# ProPrj_E73__2025-03-08.net
KiCad netlist of a schematic drawn in EasyEDA Pro
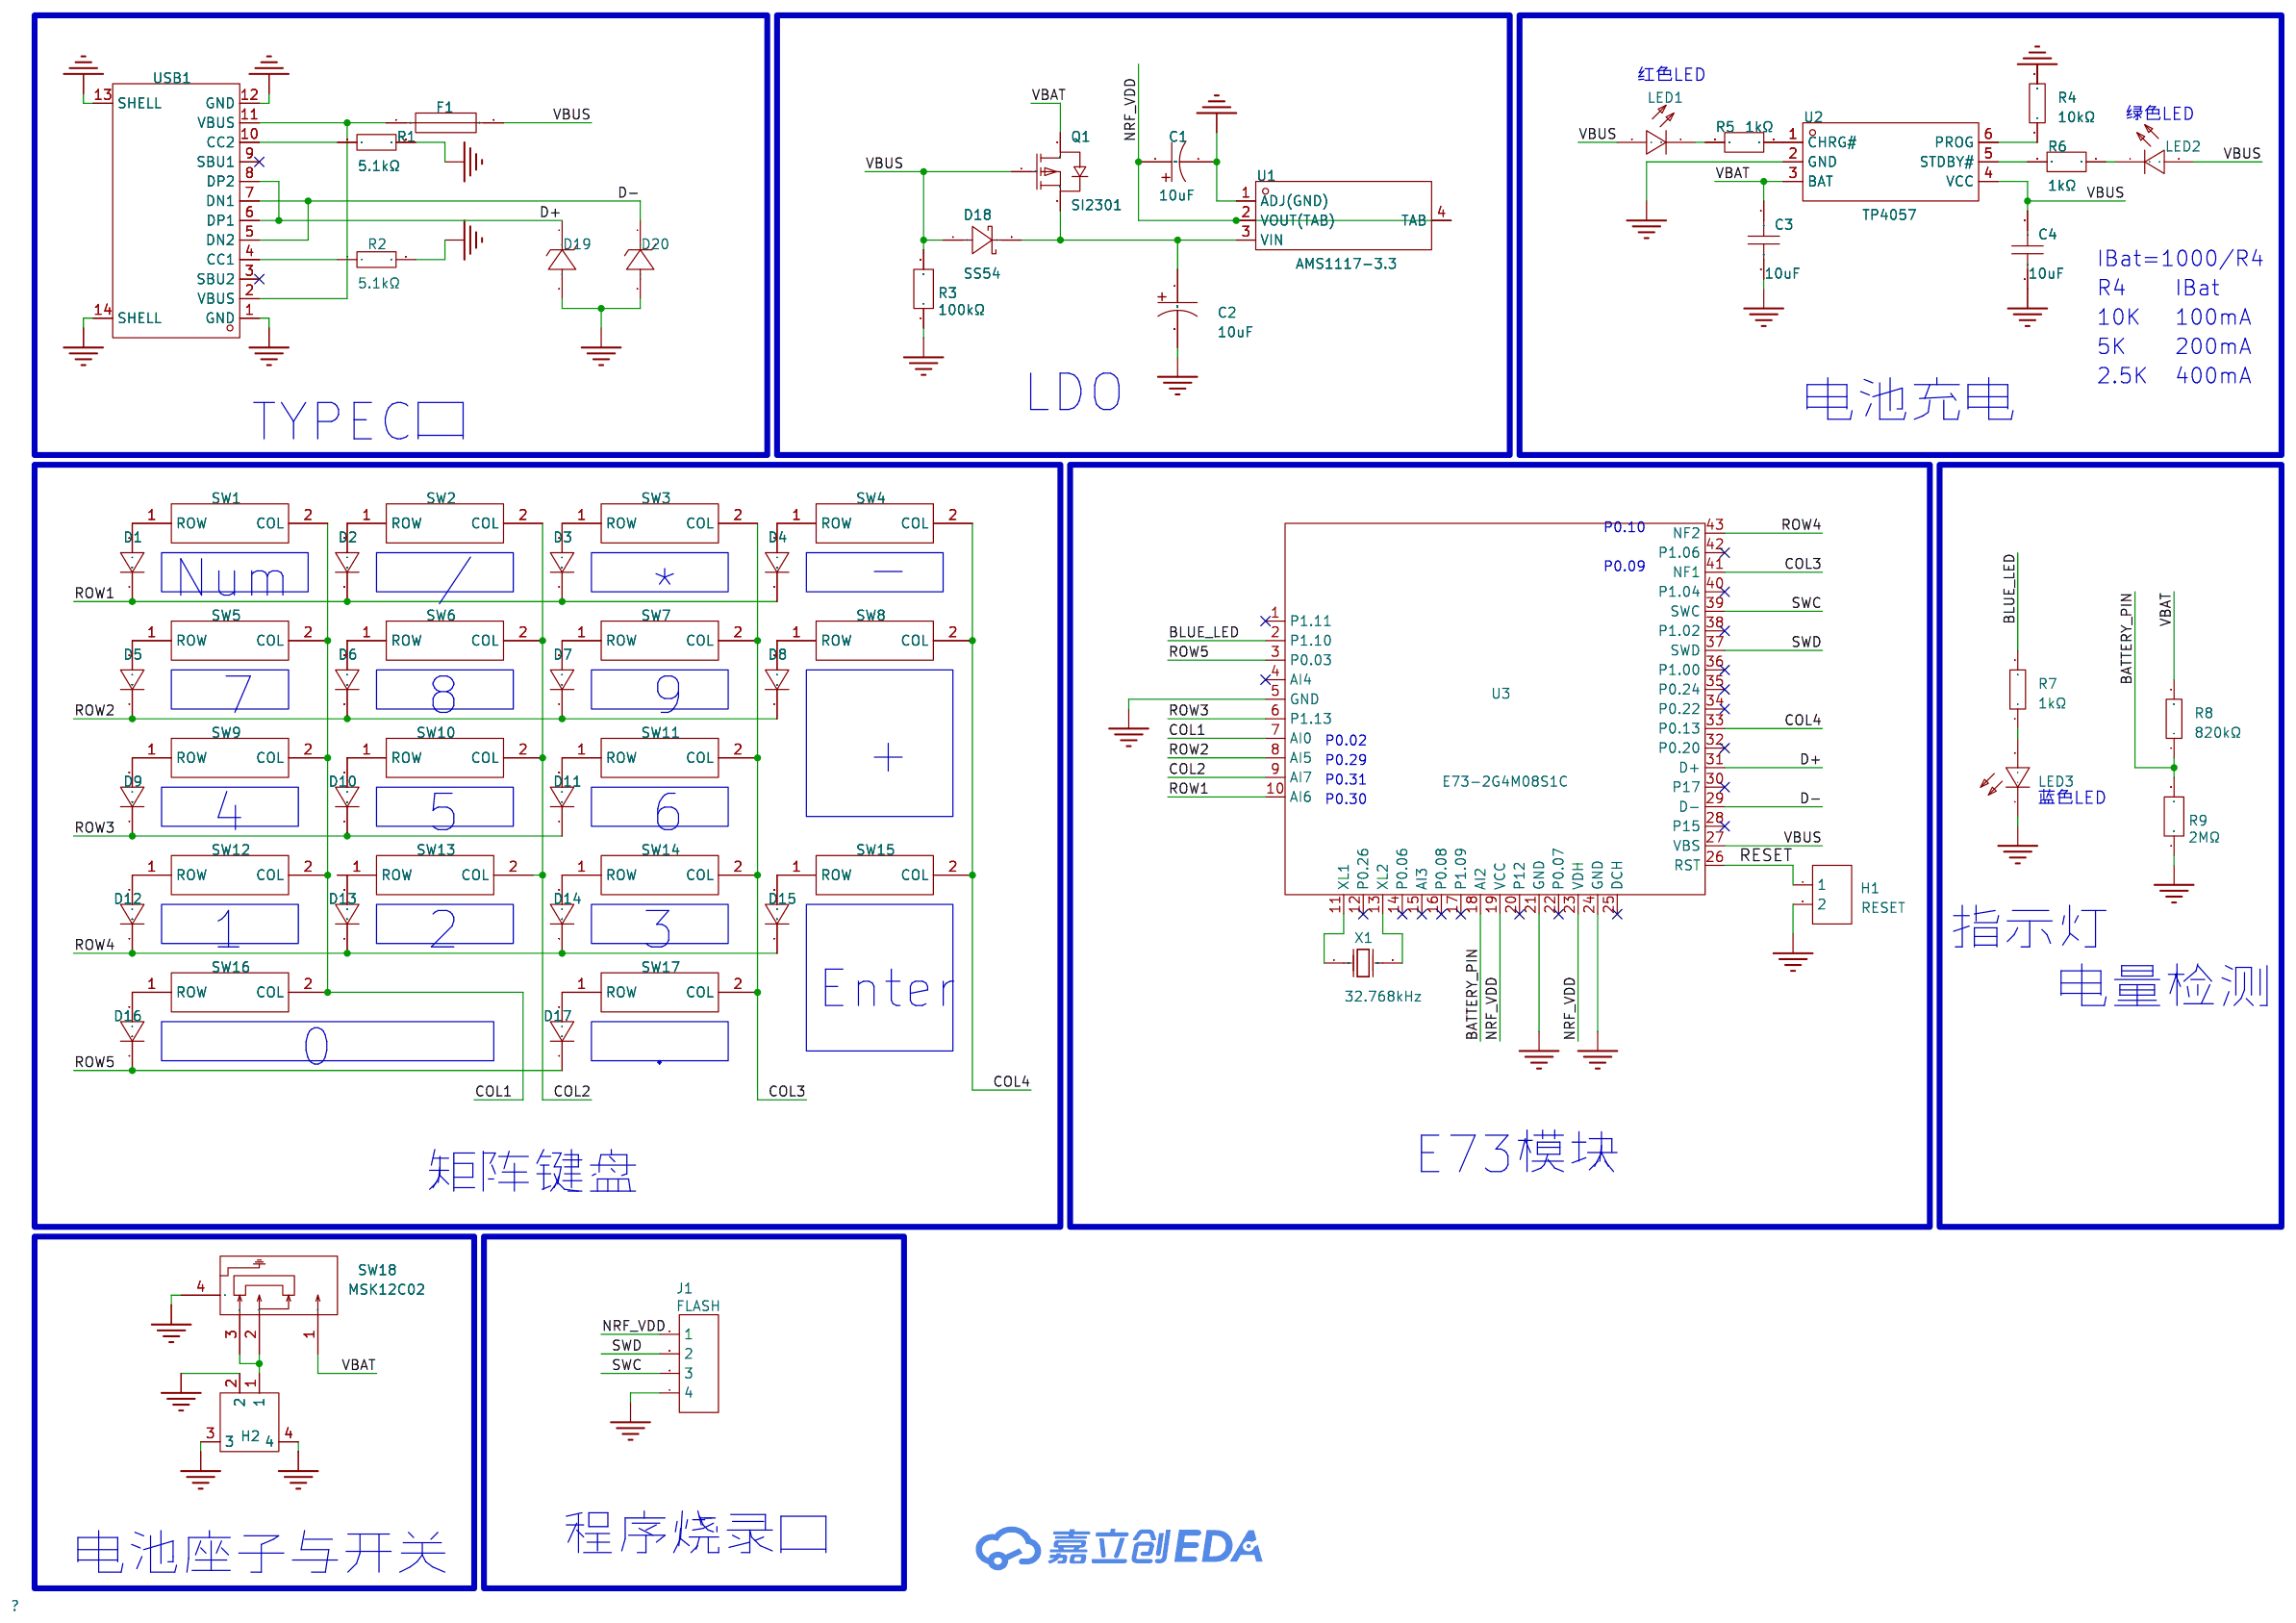
[diagram p0: schematic sheet]

(export (version "E")
  (design (tool "Eeschema 10.0.6"))
  (components
    (comp (ref "C1")
      (value "10uF")
      (footprint "easyedapro:CAP-SMD_L3.2-W1.6")
      (description "容值:10uF;精度:±10%;额定电压:16V;等效串联电阻:2Ω@100kHz;")
      (fields
        (field (name "Manufacturer Part") "CA45-A-16V-10μF-K")
        (field (name "Manufacturer") "TORCH(火炬)")
      )
      (libsource (lib "easyedapro") (part "CA45-A-16V-10μF-K"))
    )
    (comp (ref "C2")
      (value "10uF")
      (footprint "easyedapro:CAP-SMD_L3.2-W1.6")
      (description "容值:10uF;精度:±10%;额定电压:16V;等效串联电阻:2Ω@100kHz;")
      (fields
        (field (name "Manufacturer Part") "CA45-A-16V-10μF-K")
        (field (name "Manufacturer") "TORCH(火炬)")
      )
      (libsource (lib "easyedapro") (part "CA45-A-16V-10μF-K"))
    )
    (comp (ref "C3")
      (value "10uF")
      (footprint "easyedapro:C0603")
      (description "容值:10uF;精度:±20%;额定电压:16V;材质(温度系数):X5R;")
      (fields
        (field (name "Manufacturer Part") "HGC0603R5106M160NTHJ")
        (field (name "Manufacturer") "Chinocera(华瓷)")
      )
      (libsource (lib "easyedapro") (part "HGC0603R5106M160NTHJ"))
    )
    (comp (ref "C4")
      (value "10uF")
      (footprint "easyedapro:C0603")
      (description "容值:10uF;精度:±20%;额定电压:16V;材质(温度系数):X5R;")
      (fields
        (field (name "Manufacturer Part") "HGC0603R5106M160NTHJ")
        (field (name "Manufacturer") "Chinocera(华瓷)")
      )
      (libsource (lib "easyedapro") (part "HGC0603R5106M160NTHJ"))
    )
    (comp (ref "D1")
      (value "LL4148")
      (footprint "easyedapro:LL-34_L3.5-W1.5-RD")
      (description "二极管配置:-;正向压降(Vf):1V@10mA;直流反向耐压(Vr):75V;整流电流:200mA;反向恢复时间(trr):4ns;")
      (fields (field (name "Manufacturer") "MDD(辰达半导体)"))
      (libsource (lib "easyedapro") (part "LL4148_C435829"))
    )
    (comp (ref "D2")
      (value "LL4148")
      (footprint "easyedapro:LL-34_L3.5-W1.5-RD")
      (description "二极管配置:-;正向压降(Vf):1V@10mA;直流反向耐压(Vr):75V;整流电流:200mA;反向恢复时间(trr):4ns;")
      (fields (field (name "Manufacturer") "MDD(辰达半导体)"))
      (libsource (lib "easyedapro") (part "LL4148_C435829"))
    )
    (comp (ref "D3")
      (value "LL4148")
      (footprint "easyedapro:LL-34_L3.5-W1.5-RD")
      (description "二极管配置:-;正向压降(Vf):1V@10mA;直流反向耐压(Vr):75V;整流电流:200mA;反向恢复时间(trr):4ns;")
      (fields (field (name "Manufacturer") "MDD(辰达半导体)"))
      (libsource (lib "easyedapro") (part "LL4148_C435829"))
    )
    (comp (ref "D4")
      (value "LL4148")
      (footprint "easyedapro:LL-34_L3.5-W1.5-RD")
      (description "二极管配置:-;正向压降(Vf):1V@10mA;直流反向耐压(Vr):75V;整流电流:200mA;反向恢复时间(trr):4ns;")
      (fields (field (name "Manufacturer") "MDD(辰达半导体)"))
      (libsource (lib "easyedapro") (part "LL4148_C435829"))
    )
    (comp (ref "D5")
      (value "LL4148")
      (footprint "easyedapro:LL-34_L3.5-W1.5-RD")
      (description "二极管配置:-;正向压降(Vf):1V@10mA;直流反向耐压(Vr):75V;整流电流:200mA;反向恢复时间(trr):4ns;")
      (fields (field (name "Manufacturer") "MDD(辰达半导体)"))
      (libsource (lib "easyedapro") (part "LL4148_C435829"))
    )
    (comp (ref "D6")
      (value "LL4148")
      (footprint "easyedapro:LL-34_L3.5-W1.5-RD")
      (description "二极管配置:-;正向压降(Vf):1V@10mA;直流反向耐压(Vr):75V;整流电流:200mA;反向恢复时间(trr):4ns;")
      (fields (field (name "Manufacturer") "MDD(辰达半导体)"))
      (libsource (lib "easyedapro") (part "LL4148_C435829"))
    )
    (comp (ref "D7")
      (value "LL4148")
      (footprint "easyedapro:LL-34_L3.5-W1.5-RD")
      (description "二极管配置:-;正向压降(Vf):1V@10mA;直流反向耐压(Vr):75V;整流电流:200mA;反向恢复时间(trr):4ns;")
      (fields (field (name "Manufacturer") "MDD(辰达半导体)"))
      (libsource (lib "easyedapro") (part "LL4148_C435829"))
    )
    (comp (ref "D8")
      (value "LL4148")
      (footprint "easyedapro:LL-34_L3.5-W1.5-RD")
      (description "二极管配置:-;正向压降(Vf):1V@10mA;直流反向耐压(Vr):75V;整流电流:200mA;反向恢复时间(trr):4ns;")
      (fields (field (name "Manufacturer") "MDD(辰达半导体)"))
      (libsource (lib "easyedapro") (part "LL4148_C435829"))
    )
    (comp (ref "D9")
      (value "LL4148")
      (footprint "easyedapro:LL-34_L3.5-W1.5-RD")
      (description "二极管配置:-;正向压降(Vf):1V@10mA;直流反向耐压(Vr):75V;整流电流:200mA;反向恢复时间(trr):4ns;")
      (fields (field (name "Manufacturer") "MDD(辰达半导体)"))
      (libsource (lib "easyedapro") (part "LL4148_C435829"))
    )
    (comp (ref "D10")
      (value "LL4148")
      (footprint "easyedapro:LL-34_L3.5-W1.5-RD")
      (description "二极管配置:-;正向压降(Vf):1V@10mA;直流反向耐压(Vr):75V;整流电流:200mA;反向恢复时间(trr):4ns;")
      (fields (field (name "Manufacturer") "MDD(辰达半导体)"))
      (libsource (lib "easyedapro") (part "LL4148_C435829"))
    )
    (comp (ref "D11")
      (value "LL4148")
      (footprint "easyedapro:LL-34_L3.5-W1.5-RD")
      (description "二极管配置:-;正向压降(Vf):1V@10mA;直流反向耐压(Vr):75V;整流电流:200mA;反向恢复时间(trr):4ns;")
      (fields (field (name "Manufacturer") "MDD(辰达半导体)"))
      (libsource (lib "easyedapro") (part "LL4148_C435829"))
    )
    (comp (ref "D12")
      (value "LL4148")
      (footprint "easyedapro:LL-34_L3.5-W1.5-RD")
      (description "二极管配置:-;正向压降(Vf):1V@10mA;直流反向耐压(Vr):75V;整流电流:200mA;反向恢复时间(trr):4ns;")
      (fields (field (name "Manufacturer") "MDD(辰达半导体)"))
      (libsource (lib "easyedapro") (part "LL4148_C435829"))
    )
    (comp (ref "D13")
      (value "LL4148")
      (footprint "easyedapro:LL-34_L3.5-W1.5-RD")
      (description "二极管配置:-;正向压降(Vf):1V@10mA;直流反向耐压(Vr):75V;整流电流:200mA;反向恢复时间(trr):4ns;")
      (fields (field (name "Manufacturer") "MDD(辰达半导体)"))
      (libsource (lib "easyedapro") (part "LL4148_C435829"))
    )
    (comp (ref "D14")
      (value "LL4148")
      (footprint "easyedapro:LL-34_L3.5-W1.5-RD")
      (description "二极管配置:-;正向压降(Vf):1V@10mA;直流反向耐压(Vr):75V;整流电流:200mA;反向恢复时间(trr):4ns;")
      (fields (field (name "Manufacturer") "MDD(辰达半导体)"))
      (libsource (lib "easyedapro") (part "LL4148_C435829"))
    )
    (comp (ref "D15")
      (value "LL4148")
      (footprint "easyedapro:LL-34_L3.5-W1.5-RD")
      (description "二极管配置:-;正向压降(Vf):1V@10mA;直流反向耐压(Vr):75V;整流电流:200mA;反向恢复时间(trr):4ns;")
      (fields (field (name "Manufacturer") "MDD(辰达半导体)"))
      (libsource (lib "easyedapro") (part "LL4148_C435829"))
    )
    (comp (ref "D16")
      (value "LL4148")
      (footprint "easyedapro:LL-34_L3.5-W1.5-RD")
      (description "二极管配置:-;正向压降(Vf):1V@10mA;直流反向耐压(Vr):75V;整流电流:200mA;反向恢复时间(trr):4ns;")
      (fields (field (name "Manufacturer") "MDD(辰达半导体)"))
      (libsource (lib "easyedapro") (part "LL4148_C435829"))
    )
    (comp (ref "D17")
      (value "LL4148")
      (footprint "easyedapro:LL-34_L3.5-W1.5-RD")
      (description "二极管配置:-;正向压降(Vf):1V@10mA;直流反向耐压(Vr):75V;整流电流:200mA;反向恢复时间(trr):4ns;")
      (fields (field (name "Manufacturer") "MDD(辰达半导体)"))
      (libsource (lib "easyedapro") (part "LL4148_C435829"))
    )
    (comp (ref "D18")
      (value "SS54")
      (footprint "easyedapro:SMA_L4.3-W2.6-LS5.0-FD")
      (description "二极管配置:独立式;正向压降(Vf):550mV@5.0A;直流反向耐压(Vr):40V;整流电流:5A;")
      (fields (field (name "Manufacturer") "宏迦橙"))
      (libsource (lib "easyedapro") (part "SS54_C7420369"))
    )
    (comp (ref "D19")
      (value "BZT52C3V6S")
      (footprint "easyedapro:SOD-323_L1.7-W1.3-LS2.6-RD")
      (description "二极管配置:独立式;稳压值(标称值):3.6V;稳压值(范围):3.4V~3.8V;功率(Pd):200mW;")
      (fields (field (name "Manufacturer") "宏迦橙"))
      (libsource (lib "easyedapro") (part "BZT52C3V6S_C19077438"))
    )
    (comp (ref "D20")
      (value "BZT52C3V6S")
      (footprint "easyedapro:SOD-323_L1.7-W1.3-LS2.6-RD")
      (description "二极管配置:独立式;稳压值(标称值):3.6V;稳压值(范围):3.4V~3.8V;功率(Pd):200mW;")
      (fields (field (name "Manufacturer") "宏迦橙"))
      (libsource (lib "easyedapro") (part "BZT52C3V6S_C19077438"))
    )
    (comp (ref "F1")
      (value "JK-nSMD050-30")
      (footprint "easyedapro:F1206")
      (description "最大电压:30V;最大电流:100A;保持电流:500mA;跳闸电流:1A;")
      (fields (field (name "Manufacturer") "JK(金科)"))
      (libsource (lib "easyedapro") (part "JK-NSMD050-30V"))
    )
    (comp (ref "H1")
      (value "RESET")
      (footprint "easyedapro:PIN02")
      (libsource (lib "easyedapro") (part "RESET"))
    )
    (comp (ref "H2") (value "2.54-2P WT") (libsource (lib "easyedapro") (part "Battery")))
    (comp (ref "J1")
      (value "FLASH")
      (footprint "easyedapro:PIN04")
      (libsource (lib "easyedapro") (part "FLASH"))
    )
    (comp (ref "LED1")
      (value "NCD0603R1")
      (footprint "easyedapro:LED0603-RD_RED")
      (fields (field (name "Manufacturer") "国星光电"))
      (libsource (lib "easyedapro") (part "FC-DA1608HRK-620D"))
    )
    (comp (ref "LED2")
      (value "NCD0603G1")
      (footprint "easyedapro:LED0603-RD_1")
      (fields (field (name "Manufacturer") "国星光电"))
      (libsource (lib "easyedapro") (part "FC-D1608UGK-520D10"))
    )
    (comp (ref "LED3")
      (value "NCD0603B1")
      (footprint "easyedapro:LED0603-RD")
      (fields (field (name "Manufacturer") "国星光电"))
      (libsource (lib "easyedapro") (part "FC-DA1608BK-470H10"))
    )
    (comp (ref "Q1")
      (value "SI2301")
      (footprint "easyedapro:SOT-23-3_L2.9-W1.3-P1.90-LS2.4-BR")
      (fields (field (name "Manufacturer") "YONGYUTAI(永裕泰)"))
      (libsource (lib "easyedapro") (part "SI2301_C2891731"))
    )
    (comp (ref "R1")
      (value "5.1kΩ")
      (footprint "easyedapro:R0603")
      (description "电阻类型:厚膜电阻;阻值:5.1kΩ;精度:±1%;功率:100mW;最大工作电压:75V;温度系数:±100ppm/°C;")
      (fields
        (field (name "Manufacturer Part") "0603WAF5101T5E")
        (field (name "Manufacturer") "UNI-ROYAL(厚声)")
      )
      (libsource (lib "easyedapro") (part "0603WAF5101T5E"))
    )
    (comp (ref "R2")
      (value "5.1kΩ")
      (footprint "easyedapro:R0603")
      (description "电阻类型:厚膜电阻;阻值:5.1kΩ;精度:±1%;功率:100mW;最大工作电压:75V;温度系数:±100ppm/°C;")
      (fields
        (field (name "Manufacturer Part") "0603WAF5101T5E")
        (field (name "Manufacturer") "UNI-ROYAL(厚声)")
      )
      (libsource (lib "easyedapro") (part "0603WAF5101T5E"))
    )
    (comp (ref "R3")
      (value "100kΩ")
      (fields (field (name "Manufacturer") "UNI-ROYAL(厚声)"))
      (libsource (lib "easyedapro") (part "100K"))
    )
    (comp (ref "R4")
      (value "10kΩ")
      (footprint "easyedapro:R0603")
      (description "电阻类型:厚膜电阻;阻值:10kΩ;精度:±1%;功率:100mW;最大工作电压:75V;温度系数:±100ppm/°C;")
      (fields
        (field (name "Manufacturer Part") "0603WAF1002T5E")
        (field (name "Manufacturer") "UNI-ROYAL(厚声)")
      )
      (libsource (lib "easyedapro") (part "0603WAF1002T5E"))
    )
    (comp (ref "R5")
      (value "1kΩ")
      (fields (field (name "Manufacturer") "UNI-ROYAL(厚声)"))
      (libsource (lib "easyedapro") (part "1K"))
    )
    (comp (ref "R6")
      (value "1kΩ")
      (fields (field (name "Manufacturer") "UNI-ROYAL(厚声)"))
      (libsource (lib "easyedapro") (part "1K"))
    )
    (comp (ref "R7")
      (value "1kΩ")
      (footprint "easyedapro:R0603")
      (description "电阻类型:厚膜电阻;阻值:1kΩ;精度:±1%;功率:100mW;最大工作电压:75V;温度系数:±100ppm/°C;")
      (fields
        (field (name "Manufacturer Part") "0603WAF1001T5E")
        (field (name "Manufacturer") "UNI-ROYAL(厚声)")
      )
      (libsource (lib "easyedapro") (part "0603WAF1001T5E"))
    )
    (comp (ref "R8")
      (value "820kΩ")
      (footprint "easyedapro:R0603")
      (description "电阻类型:厚膜电阻;阻值:820kΩ;精度:±1%;功率:100mW;最大工作电压:75V;温度系数:±100ppm/°C;")
      (fields
        (field (name "Manufacturer Part") "0603WAF8203T5E")
        (field (name "Manufacturer") "UNI-ROYAL(厚声)")
      )
      (libsource (lib "easyedapro") (part "0603WAF8203T5E"))
    )
    (comp (ref "R9")
      (value "2MΩ")
      (fields (field (name "Manufacturer") "UNI-ROYAL(厚声)"))
      (libsource (lib "easyedapro") (part "2M"))
    )
    (comp (ref "SW1")
      (value "~")
      (footprint "easyedapro:键盘轴座(无灯)")
      (libsource (lib "easyedapro") (part "键盘轴座(无灯)"))
    )
    (comp (ref "SW2")
      (value "~")
      (footprint "easyedapro:键盘轴座(无灯)")
      (libsource (lib "easyedapro") (part "键盘轴座(无灯)"))
    )
    (comp (ref "SW3")
      (value "~")
      (footprint "easyedapro:键盘轴座(无灯)")
      (libsource (lib "easyedapro") (part "键盘轴座(无灯)"))
    )
    (comp (ref "SW4")
      (value "~")
      (footprint "easyedapro:键盘轴座(无灯)")
      (libsource (lib "easyedapro") (part "键盘轴座(无灯)"))
    )
    (comp (ref "SW5")
      (value "~")
      (footprint "easyedapro:键盘轴座(无灯)")
      (libsource (lib "easyedapro") (part "键盘轴座(无灯)"))
    )
    (comp (ref "SW6")
      (value "~")
      (footprint "easyedapro:键盘轴座(无灯)")
      (libsource (lib "easyedapro") (part "键盘轴座(无灯)"))
    )
    (comp (ref "SW7")
      (value "~")
      (footprint "easyedapro:键盘轴座(无灯)")
      (libsource (lib "easyedapro") (part "键盘轴座(无灯)"))
    )
    (comp (ref "SW8")
      (value "~")
      (footprint "easyedapro:键盘轴座(无灯)")
      (libsource (lib "easyedapro") (part "键盘轴座(无灯)"))
    )
    (comp (ref "SW9")
      (value "~")
      (footprint "easyedapro:键盘轴座(无灯)")
      (libsource (lib "easyedapro") (part "键盘轴座(无灯)"))
    )
    (comp (ref "SW10")
      (value "~")
      (footprint "easyedapro:键盘轴座(无灯)")
      (libsource (lib "easyedapro") (part "键盘轴座(无灯)"))
    )
    (comp (ref "SW11")
      (value "~")
      (footprint "easyedapro:键盘轴座(无灯)")
      (libsource (lib "easyedapro") (part "键盘轴座(无灯)"))
    )
    (comp (ref "SW12")
      (value "~")
      (footprint "easyedapro:键盘轴座(无灯)")
      (libsource (lib "easyedapro") (part "键盘轴座(无灯)"))
    )
    (comp (ref "SW13")
      (value "~")
      (footprint "easyedapro:键盘轴座(无灯)")
      (libsource (lib "easyedapro") (part "键盘轴座(无灯)"))
    )
    (comp (ref "SW14")
      (value "~")
      (footprint "easyedapro:键盘轴座(无灯)")
      (libsource (lib "easyedapro") (part "键盘轴座(无灯)"))
    )
    (comp (ref "SW15")
      (value "~")
      (footprint "easyedapro:键盘轴座(无灯)")
      (libsource (lib "easyedapro") (part "键盘轴座(无灯)"))
    )
    (comp (ref "SW16")
      (value "~")
      (footprint "easyedapro:键盘轴座(无灯)")
      (libsource (lib "easyedapro") (part "键盘轴座(无灯)"))
    )
    (comp (ref "SW17")
      (value "~")
      (footprint "easyedapro:键盘轴座(无灯)")
      (libsource (lib "easyedapro") (part "键盘轴座(无灯)"))
    )
    (comp (ref "SW18")
      (value "MSK12C02")
      (footprint "easyedapro:SW-TH_MSK12C02")
      (description "电路结构:单刀双掷;安装方式:卧贴;开关颜色:-;额定电流(DC):50mA;额定电压(DC):12V;额定电流(AC):-;额定电压(AC):-;机械寿命:1万次;")
      (fields (field (name "Manufacturer") "SHOU HAN(首韩)"))
      (libsource (lib "easyedapro") (part "MSK12C02"))
    )
    (comp (ref "U1")
      (value "AMS1117-3.3")
      (footprint "easyedapro:SOT-223-4_L6.5-W3.5-P2.30-LS7.0-BR")
      (description "输出类型:固定;工作电压:12V;输出电压:3.3V;输出电流:1A;电源纹波抑制比(PSRR):60dB@(120Hz);输出极性:正极;")
      (fields (field (name "Manufacturer") "UMW(友台半导体)"))
      (libsource (lib "easyedapro") (part "AMS1117-3.3_C347222"))
    )
    (comp (ref "U2")
      (value "TP4057")
      (footprint "easyedapro:SOT-23-6_L2.9-W1.6-P0.95-LS2.8-BR")
      (description "电源电压:6.5V;最大充电电流:500mA;电池类型:锂离子/聚合物;电池节数:1;")
      (fields (field (name "Manufacturer") "UMW(友台半导体)"))
      (libsource (lib "easyedapro") (part "TP4057_C725791"))
    )
    (comp (ref "U3")
      (value "E73-2G4M08S1C")
      (footprint "easyedapro:WIRELM-SMD_E73-2G4M08S1C")
      (fields (field (name "Manufacturer") "EBYTE(亿佰特)"))
      (libsource (lib "easyedapro") (part "E73-2G4M08S1C"))
    )
    (comp (ref "USB1")
      (value "TYPE-C 16PIN 2MD(073)")
      (footprint "easyedapro:USB-C-SMD_TYPE-C-6PIN-2MD-073")
      (description "连接器类型:Type-C;标准:USB 3.1;公母:母;安装方式:卧贴;触点数量:16P;端口数量:1;额定电流 - 电源:5A;工作温度范围:-25°C~+85°C;")
      (fields (field (name "Manufacturer") "SHOU HAN(首韩)"))
      (libsource (lib "easyedapro") (part "TYPE-C 16PIN 2MD(073)"))
    )
    (comp (ref "X1")
      (value "32.768kHz")
      (footprint "easyedapro:CRYSTAL-SMD_L3.2-W1.5-1")
      (description "晶振类型:贴片晶振;频率:32.768kHz;常温频差:±20ppm;负载电容:12.5pF;频率稳定度:±30ppm;")
      (fields
        (field (name "Manufacturer Part") "XKXGI-SUA-32.768K")
        (field (name "Manufacturer") "YXC(扬兴晶振)")
      )
      (libsource (lib "easyedapro") (part "XKXGI-SUA-32.768K"))
    )
  )
  (nets
    (net (code "1") (name "/BATTERY_PIN") (class "Default")
      (node (ref "R8") (pin "1") (pinfunction "1_1") (pintype "input"))
      (node (ref "R9") (pin "2") (pinfunction "2_2") (pintype "unspecified"))
      (node (ref "U3") (pin "18") (pinfunction "AI2_18") (pintype "unspecified"))
    )
    (net (code "2") (name "/BLUE_LED") (class "Default")
      (node (ref "R7") (pin "2") (pinfunction "2_2") (pintype "input"))
      (node (ref "U3") (pin "2") (pinfunction "P1.10_2") (pintype "unspecified"))
    )
    (net (code "3") (name "/COL1") (class "Default")
      (node (ref "SW1") (pin "2") (pinfunction "COL_2") (pintype "input"))
      (node (ref "SW12") (pin "2") (pinfunction "COL_2") (pintype "input"))
      (node (ref "SW16") (pin "2") (pinfunction "COL_2") (pintype "input"))
      (node (ref "SW5") (pin "2") (pinfunction "COL_2") (pintype "input"))
      (node (ref "SW9") (pin "2") (pinfunction "COL_2") (pintype "input"))
      (node (ref "U3") (pin "7") (pinfunction "AI0_7") (pintype "unspecified"))
    )
    (net (code "4") (name "/COL2") (class "Default")
      (node (ref "SW10") (pin "2") (pinfunction "COL_2") (pintype "input"))
      (node (ref "SW13") (pin "2") (pinfunction "COL_2") (pintype "input"))
      (node (ref "SW2") (pin "2") (pinfunction "COL_2") (pintype "input"))
      (node (ref "SW6") (pin "2") (pinfunction "COL_2") (pintype "input"))
      (node (ref "U3") (pin "9") (pinfunction "AI7_9") (pintype "unspecified"))
    )
    (net (code "5") (name "/COL3") (class "Default")
      (node (ref "SW11") (pin "2") (pinfunction "COL_2") (pintype "input"))
      (node (ref "SW14") (pin "2") (pinfunction "COL_2") (pintype "input"))
      (node (ref "SW17") (pin "2") (pinfunction "COL_2") (pintype "input"))
      (node (ref "SW3") (pin "2") (pinfunction "COL_2") (pintype "input"))
      (node (ref "SW7") (pin "2") (pinfunction "COL_2") (pintype "input"))
      (node (ref "U3") (pin "41") (pinfunction "NF1_41") (pintype "unspecified"))
    )
    (net (code "6") (name "/COL4") (class "Default")
      (node (ref "SW15") (pin "2") (pinfunction "COL_2") (pintype "input"))
      (node (ref "SW4") (pin "2") (pinfunction "COL_2") (pintype "input"))
      (node (ref "SW8") (pin "2") (pinfunction "COL_2") (pintype "input"))
      (node (ref "U3") (pin "33") (pinfunction "P0.13_33") (pintype "unspecified"))
    )
    (net (code "7") (name "/D+") (class "Default")
      (node (ref "D19") (pin "1") (pinfunction "K_1") (pintype "unspecified"))
      (node (ref "U3") (pin "31") (pinfunction "D+_31") (pintype "unspecified"))
      (node (ref "USB1") (pin "6") (pinfunction "DP1_6") (pintype "unspecified"))
      (node (ref "USB1") (pin "8") (pinfunction "DP2_8") (pintype "unspecified"))
    )
    (net (code "8") (name "/D-") (class "Default")
      (node (ref "D20") (pin "1") (pinfunction "K_1") (pintype "unspecified"))
      (node (ref "U3") (pin "29") (pinfunction "D-_29") (pintype "unspecified"))
      (node (ref "USB1") (pin "5") (pinfunction "DN2_5") (pintype "unspecified"))
      (node (ref "USB1") (pin "7") (pinfunction "DN1_7") (pintype "unspecified"))
    )
    (net (code "9") (name "/NRF_VDD") (class "Default")
      (node (ref "C1") (pin "1") (pinfunction "1_1") (pintype "unspecified"))
      (node (ref "J1") (pin "1") (pinfunction "1_1") (pintype "unspecified"))
      (node (ref "U1") (pin "2") (pinfunction "VOUT(TAB)_2") (pintype "unspecified"))
      (node (ref "U1") (pin "4") (pinfunction "TAB_4") (pintype "unspecified"))
      (node (ref "U3") (pin "19") (pinfunction "VCC_19") (pintype "unspecified"))
      (node (ref "U3") (pin "23") (pinfunction "VDH_23") (pintype "unspecified"))
    )
    (net (code "10") (name "/RESET") (class "Default")
      (node (ref "H1") (pin "1") (pinfunction "1_1") (pintype "input"))
      (node (ref "U3") (pin "26") (pinfunction "RST_26") (pintype "unspecified"))
    )
    (net (code "11") (name "/ROW1") (class "Default")
      (node (ref "D1") (pin "1") (pinfunction "C_1") (pintype "unspecified"))
      (node (ref "D2") (pin "1") (pinfunction "C_1") (pintype "unspecified"))
      (node (ref "D3") (pin "1") (pinfunction "C_1") (pintype "unspecified"))
      (node (ref "D4") (pin "1") (pinfunction "C_1") (pintype "unspecified"))
      (node (ref "U3") (pin "10") (pinfunction "AI6_10") (pintype "unspecified"))
    )
    (net (code "12") (name "/ROW2") (class "Default")
      (node (ref "D5") (pin "1") (pinfunction "C_1") (pintype "unspecified"))
      (node (ref "D6") (pin "1") (pinfunction "C_1") (pintype "unspecified"))
      (node (ref "D7") (pin "1") (pinfunction "C_1") (pintype "unspecified"))
      (node (ref "D8") (pin "1") (pinfunction "C_1") (pintype "unspecified"))
      (node (ref "U3") (pin "8") (pinfunction "AI5_8") (pintype "unspecified"))
    )
    (net (code "13") (name "/ROW3") (class "Default")
      (node (ref "D10") (pin "1") (pinfunction "C_1") (pintype "unspecified"))
      (node (ref "D11") (pin "1") (pinfunction "C_1") (pintype "unspecified"))
      (node (ref "D9") (pin "1") (pinfunction "C_1") (pintype "unspecified"))
      (node (ref "U3") (pin "6") (pinfunction "P1.13_6") (pintype "unspecified"))
    )
    (net (code "14") (name "/ROW4") (class "Default")
      (node (ref "D12") (pin "1") (pinfunction "C_1") (pintype "unspecified"))
      (node (ref "D13") (pin "1") (pinfunction "C_1") (pintype "unspecified"))
      (node (ref "D14") (pin "1") (pinfunction "C_1") (pintype "unspecified"))
      (node (ref "D15") (pin "1") (pinfunction "C_1") (pintype "unspecified"))
      (node (ref "U3") (pin "43") (pinfunction "NF2_43") (pintype "unspecified"))
    )
    (net (code "15") (name "/ROW5") (class "Default")
      (node (ref "D16") (pin "1") (pinfunction "C_1") (pintype "unspecified"))
      (node (ref "D17") (pin "1") (pinfunction "C_1") (pintype "unspecified"))
      (node (ref "U3") (pin "3") (pinfunction "P0.03_3") (pintype "unspecified"))
    )
    (net (code "16") (name "/SWC") (class "Default")
      (node (ref "J1") (pin "3") (pinfunction "3_3") (pintype "unspecified"))
      (node (ref "U3") (pin "39") (pinfunction "SWC_39") (pintype "unspecified"))
    )
    (net (code "17") (name "/SWD") (class "Default")
      (node (ref "J1") (pin "2") (pinfunction "2_2") (pintype "unspecified"))
      (node (ref "U3") (pin "37") (pinfunction "SWD_37") (pintype "unspecified"))
    )
    (net (code "18") (name "/VBAT") (class "Default")
      (node (ref "C3") (pin "1") (pinfunction "1_1") (pintype "unspecified"))
      (node (ref "Q1") (pin "3") (pinfunction "D_3") (pintype "unspecified"))
      (node (ref "R8") (pin "2") (pinfunction "2_2") (pintype "input"))
      (node (ref "SW18") (pin "1") (pinfunction "1_1") (pintype "unspecified"))
      (node (ref "U2") (pin "3") (pinfunction "BAT_3") (pintype "unspecified"))
    )
    (net (code "19") (name "/VBUS") (class "Default")
      (node (ref "C4") (pin "2") (pinfunction "2_2") (pintype "unspecified"))
      (node (ref "D18") (pin "1") (pinfunction "A_1") (pintype "unspecified"))
      (node (ref "F1") (pin "2") (pinfunction "2_2") (pintype "unspecified"))
      (node (ref "LED1") (pin "2") (pinfunction "A_2") (pintype "input"))
      (node (ref "LED2") (pin "2") (pinfunction "A_2") (pintype "input"))
      (node (ref "Q1") (pin "1") (pinfunction "G_1") (pintype "unspecified"))
      (node (ref "R3") (pin "2") (pinfunction "2_2") (pintype "unspecified"))
      (node (ref "U2") (pin "4") (pinfunction "VCC_4") (pintype "unspecified"))
      (node (ref "U3") (pin "27") (pinfunction "VBS_27") (pintype "unspecified"))
    )
    (net (code "20") (name "GND") (class "Default")
      (node (ref "C1") (pin "2") (pinfunction "2_2") (pintype "unspecified"))
      (node (ref "C2") (pin "2") (pinfunction "2_2") (pintype "unspecified"))
      (node (ref "C3") (pin "2") (pinfunction "2_2") (pintype "unspecified"))
      (node (ref "C4") (pin "1") (pinfunction "1_1") (pintype "unspecified"))
      (node (ref "D19") (pin "2") (pinfunction "A_2") (pintype "unspecified"))
      (node (ref "D20") (pin "2") (pinfunction "A_2") (pintype "unspecified"))
      (node (ref "H1") (pin "2") (pinfunction "2_2") (pintype "input"))
      (node (ref "H2") (pin "2") (pinfunction "2_2") (pintype "unspecified"))
      (node (ref "H2") (pin "3") (pinfunction "3_3") (pintype "unspecified"))
      (node (ref "H2") (pin "4") (pinfunction "4_4") (pintype "unspecified"))
      (node (ref "J1") (pin "4") (pinfunction "4_4") (pintype "unspecified"))
      (node (ref "LED3") (pin "1") (pinfunction "-_1") (pintype "input"))
      (node (ref "R1") (pin "2") (pinfunction "2_2") (pintype "input"))
      (node (ref "R2") (pin "2") (pinfunction "2_2") (pintype "input"))
      (node (ref "R3") (pin "1") (pinfunction "1_1") (pintype "unspecified"))
      (node (ref "R4") (pin "2") (pinfunction "2_2") (pintype "input"))
      (node (ref "R9") (pin "1") (pinfunction "1_1") (pintype "unspecified"))
      (node (ref "SW18") (pin "4") (pinfunction "4_4") (pintype "unspecified"))
      (node (ref "U1") (pin "1") (pinfunction "ADJ(GND)_1") (pintype "unspecified"))
      (node (ref "U2") (pin "2") (pinfunction "GND_2") (pintype "unspecified"))
      (node (ref "U3") (pin "21") (pinfunction "GND_21") (pintype "unspecified"))
      (node (ref "U3") (pin "24") (pinfunction "GND_24") (pintype "unspecified"))
      (node (ref "U3") (pin "5") (pinfunction "GND_5") (pintype "unspecified"))
      (node (ref "USB1") (pin "1") (pinfunction "GND_1") (pintype "unspecified"))
      (node (ref "USB1") (pin "12") (pinfunction "GND_12") (pintype "unspecified"))
      (node (ref "USB1") (pin "13") (pinfunction "SHELL_13") (pintype "unspecified"))
      (node (ref "USB1") (pin "14") (pinfunction "SHELL_14") (pintype "unspecified"))
    )
    (net (code "21") (name "Net-(D1-A)") (class "Default")
      (node (ref "D1") (pin "2") (pinfunction "A_2") (pintype "unspecified"))
      (node (ref "SW1") (pin "1") (pinfunction "ROW_1") (pintype "input"))
    )
    (net (code "22") (name "Net-(D2-A)") (class "Default")
      (node (ref "D2") (pin "2") (pinfunction "A_2") (pintype "unspecified"))
      (node (ref "SW2") (pin "1") (pinfunction "ROW_1") (pintype "input"))
    )
    (net (code "23") (name "Net-(D3-A)") (class "Default")
      (node (ref "D3") (pin "2") (pinfunction "A_2") (pintype "unspecified"))
      (node (ref "SW3") (pin "1") (pinfunction "ROW_1") (pintype "input"))
    )
    (net (code "24") (name "Net-(D4-A)") (class "Default")
      (node (ref "D4") (pin "2") (pinfunction "A_2") (pintype "unspecified"))
      (node (ref "SW4") (pin "1") (pinfunction "ROW_1") (pintype "input"))
    )
    (net (code "25") (name "Net-(D5-A)") (class "Default")
      (node (ref "D5") (pin "2") (pinfunction "A_2") (pintype "unspecified"))
      (node (ref "SW5") (pin "1") (pinfunction "ROW_1") (pintype "input"))
    )
    (net (code "26") (name "Net-(D6-A)") (class "Default")
      (node (ref "D6") (pin "2") (pinfunction "A_2") (pintype "unspecified"))
      (node (ref "SW6") (pin "1") (pinfunction "ROW_1") (pintype "input"))
    )
    (net (code "27") (name "Net-(D7-A)") (class "Default")
      (node (ref "D7") (pin "2") (pinfunction "A_2") (pintype "unspecified"))
      (node (ref "SW7") (pin "1") (pinfunction "ROW_1") (pintype "input"))
    )
    (net (code "28") (name "Net-(D8-A)") (class "Default")
      (node (ref "D8") (pin "2") (pinfunction "A_2") (pintype "unspecified"))
      (node (ref "SW8") (pin "1") (pinfunction "ROW_1") (pintype "input"))
    )
    (net (code "29") (name "Net-(D9-A)") (class "Default")
      (node (ref "D9") (pin "2") (pinfunction "A_2") (pintype "unspecified"))
      (node (ref "SW9") (pin "1") (pinfunction "ROW_1") (pintype "input"))
    )
    (net (code "30") (name "Net-(D10-A)") (class "Default")
      (node (ref "D10") (pin "2") (pinfunction "A_2") (pintype "unspecified"))
      (node (ref "SW10") (pin "1") (pinfunction "ROW_1") (pintype "input"))
    )
    (net (code "31") (name "Net-(D11-A)") (class "Default")
      (node (ref "D11") (pin "2") (pinfunction "A_2") (pintype "unspecified"))
      (node (ref "SW11") (pin "1") (pinfunction "ROW_1") (pintype "input"))
    )
    (net (code "32") (name "Net-(D12-A)") (class "Default")
      (node (ref "D12") (pin "2") (pinfunction "A_2") (pintype "unspecified"))
      (node (ref "SW12") (pin "1") (pinfunction "ROW_1") (pintype "input"))
    )
    (net (code "33") (name "Net-(D13-A)") (class "Default")
      (node (ref "D13") (pin "2") (pinfunction "A_2") (pintype "unspecified"))
      (node (ref "SW13") (pin "1") (pinfunction "ROW_1") (pintype "input"))
    )
    (net (code "34") (name "Net-(D14-A)") (class "Default")
      (node (ref "D14") (pin "2") (pinfunction "A_2") (pintype "unspecified"))
      (node (ref "SW14") (pin "1") (pinfunction "ROW_1") (pintype "input"))
    )
    (net (code "35") (name "Net-(D15-A)") (class "Default")
      (node (ref "D15") (pin "2") (pinfunction "A_2") (pintype "unspecified"))
      (node (ref "SW15") (pin "1") (pinfunction "ROW_1") (pintype "input"))
    )
    (net (code "36") (name "Net-(D16-A)") (class "Default")
      (node (ref "D16") (pin "2") (pinfunction "A_2") (pintype "unspecified"))
      (node (ref "SW16") (pin "1") (pinfunction "ROW_1") (pintype "input"))
    )
    (net (code "37") (name "Net-(D17-A)") (class "Default")
      (node (ref "D17") (pin "2") (pinfunction "A_2") (pintype "unspecified"))
      (node (ref "SW17") (pin "1") (pinfunction "ROW_1") (pintype "input"))
    )
    (net (code "38") (name "Net-(D18-K)") (class "Default")
      (node (ref "C2") (pin "1") (pinfunction "1_1") (pintype "unspecified"))
      (node (ref "D18") (pin "2") (pinfunction "K_2") (pintype "unspecified"))
      (node (ref "Q1") (pin "2") (pinfunction "S_2") (pintype "unspecified"))
      (node (ref "U1") (pin "3") (pinfunction "VIN_3") (pintype "unspecified"))
    )
    (net (code "39") (name "Net-(F1-Pad1)") (class "Default")
      (node (ref "F1") (pin "1") (pinfunction "1_1") (pintype "unspecified"))
      (node (ref "USB1") (pin "11") (pinfunction "VBUS_11") (pintype "unspecified"))
      (node (ref "USB1") (pin "2") (pinfunction "VBUS_2") (pintype "unspecified"))
    )
    (net (code "40") (name "Net-(H2-Pad1)") (class "Default")
      (node (ref "H2") (pin "1") (pinfunction "1_1") (pintype "unspecified"))
      (node (ref "SW18") (pin "2") (pinfunction "2_2") (pintype "unspecified"))
      (node (ref "SW18") (pin "3") (pinfunction "3_3") (pintype "unspecified"))
    )
    (net (code "41") (name "Net-(LED1-K)") (class "Default")
      (node (ref "LED1") (pin "1") (pinfunction "K_1") (pintype "input"))
      (node (ref "R5") (pin "1") (pinfunction "1_1") (pintype "unspecified"))
    )
    (net (code "42") (name "Net-(LED2-K)") (class "Default")
      (node (ref "LED2") (pin "1") (pinfunction "K_1") (pintype "input"))
      (node (ref "R6") (pin "1") (pinfunction "1_1") (pintype "unspecified"))
    )
    (net (code "43") (name "Net-(LED3-+)") (class "Default")
      (node (ref "LED3") (pin "2") (pinfunction "+_2") (pintype "input"))
      (node (ref "R7") (pin "1") (pinfunction "1_1") (pintype "input"))
    )
    (net (code "44") (name "Net-(U2-CHRG#)") (class "Default")
      (node (ref "R5") (pin "2") (pinfunction "2_2") (pintype "unspecified"))
      (node (ref "U2") (pin "1") (pinfunction "CHRG#_1") (pintype "unspecified"))
    )
    (net (code "45") (name "Net-(U2-PROG)") (class "Default")
      (node (ref "R4") (pin "1") (pinfunction "1_1") (pintype "input"))
      (node (ref "U2") (pin "6") (pinfunction "PROG_6") (pintype "unspecified"))
    )
    (net (code "46") (name "Net-(U2-STDBY#)") (class "Default")
      (node (ref "R6") (pin "2") (pinfunction "2_2") (pintype "unspecified"))
      (node (ref "U2") (pin "5") (pinfunction "STDBY#_5") (pintype "unspecified"))
    )
    (net (code "47") (name "Net-(U3-XL1)") (class "Default")
      (node (ref "U3") (pin "11") (pinfunction "XL1_11") (pintype "unspecified"))
      (node (ref "X1") (pin "1") (pinfunction "OSC1_1") (pintype "input"))
    )
    (net (code "48") (name "Net-(U3-XL2)") (class "Default")
      (node (ref "U3") (pin "13") (pinfunction "XL2_13") (pintype "unspecified"))
      (node (ref "X1") (pin "2") (pinfunction "OSC2_2") (pintype "input"))
    )
    (net (code "49") (name "Net-(USB1-CC1)") (class "Default")
      (node (ref "R2") (pin "1") (pinfunction "1_1") (pintype "input"))
      (node (ref "USB1") (pin "4") (pinfunction "CC1_4") (pintype "unspecified"))
    )
    (net (code "50") (name "Net-(USB1-CC2)") (class "Default")
      (node (ref "R1") (pin "1") (pinfunction "1_1") (pintype "input"))
      (node (ref "USB1") (pin "10") (pinfunction "CC2_10") (pintype "unspecified"))
    )
    (net (code "51") (name "unconnected-(U3-AI3-Pad15)") (class "Default")
      (node (ref "U3") (pin "15") (pinfunction "AI3_15") (pintype "unspecified+no_connect"))
    )
    (net (code "52") (name "unconnected-(U3-AI4-Pad4)") (class "Default")
      (node (ref "U3") (pin "4") (pinfunction "AI4_4") (pintype "unspecified+no_connect"))
    )
    (net (code "53") (name "unconnected-(U3-DCH-Pad25)") (class "Default")
      (node (ref "U3") (pin "25") (pinfunction "DCH_25") (pintype "unspecified+no_connect"))
    )
    (net (code "54") (name "unconnected-(U3-P0.06-Pad14)") (class "Default")
      (node (ref "U3") (pin "14") (pinfunction "P0.06_14") (pintype "unspecified+no_connect"))
    )
    (net (code "55") (name "unconnected-(U3-P0.07-Pad22)") (class "Default")
      (node (ref "U3") (pin "22") (pinfunction "P0.07_22") (pintype "unspecified+no_connect"))
    )
    (net (code "56") (name "unconnected-(U3-P0.08-Pad16)") (class "Default")
      (node (ref "U3") (pin "16") (pinfunction "P0.08_16") (pintype "unspecified+no_connect"))
    )
    (net (code "57") (name "unconnected-(U3-P0.20-Pad32)") (class "Default")
      (node (ref "U3") (pin "32") (pinfunction "P0.20_32") (pintype "unspecified+no_connect"))
    )
    (net (code "58") (name "unconnected-(U3-P0.22-Pad34)") (class "Default")
      (node (ref "U3") (pin "34") (pinfunction "P0.22_34") (pintype "unspecified+no_connect"))
    )
    (net (code "59") (name "unconnected-(U3-P0.24-Pad35)") (class "Default")
      (node (ref "U3") (pin "35") (pinfunction "P0.24_35") (pintype "unspecified+no_connect"))
    )
    (net (code "60") (name "unconnected-(U3-P0.26-Pad12)") (class "Default")
      (node (ref "U3") (pin "12") (pinfunction "P0.26_12") (pintype "unspecified+no_connect"))
    )
    (net (code "61") (name "unconnected-(U3-P1.00-Pad36)") (class "Default")
      (node (ref "U3") (pin "36") (pinfunction "P1.00_36") (pintype "unspecified+no_connect"))
    )
    (net (code "62") (name "unconnected-(U3-P1.02-Pad38)") (class "Default")
      (node (ref "U3") (pin "38") (pinfunction "P1.02_38") (pintype "unspecified+no_connect"))
    )
    (net (code "63") (name "unconnected-(U3-P1.04-Pad40)") (class "Default")
      (node (ref "U3") (pin "40") (pinfunction "P1.04_40") (pintype "unspecified+no_connect"))
    )
    (net (code "64") (name "unconnected-(U3-P1.06-Pad42)") (class "Default")
      (node (ref "U3") (pin "42") (pinfunction "P1.06_42") (pintype "unspecified+no_connect"))
    )
    (net (code "65") (name "unconnected-(U3-P1.09-Pad17)") (class "Default")
      (node (ref "U3") (pin "17") (pinfunction "P1.09_17") (pintype "unspecified+no_connect"))
    )
    (net (code "66") (name "unconnected-(U3-P1.11-Pad1)") (class "Default")
      (node (ref "U3") (pin "1") (pinfunction "P1.11_1") (pintype "unspecified+no_connect"))
    )
    (net (code "67") (name "unconnected-(U3-P12-Pad20)") (class "Default")
      (node (ref "U3") (pin "20") (pinfunction "P12_20") (pintype "unspecified+no_connect"))
    )
    (net (code "68") (name "unconnected-(U3-P15-Pad28)") (class "Default")
      (node (ref "U3") (pin "28") (pinfunction "P15_28") (pintype "unspecified+no_connect"))
    )
    (net (code "69") (name "unconnected-(U3-P17-Pad30)") (class "Default")
      (node (ref "U3") (pin "30") (pinfunction "P17_30") (pintype "unspecified+no_connect"))
    )
    (net (code "70") (name "unconnected-(USB1-SBU1-Pad9)") (class "Default")
      (node (ref "USB1") (pin "9") (pinfunction "SBU1_9") (pintype "unspecified+no_connect"))
    )
    (net (code "71") (name "unconnected-(USB1-SBU2-Pad3)") (class "Default")
      (node (ref "USB1") (pin "3") (pinfunction "SBU2_3") (pintype "unspecified+no_connect"))
    )
  )
)
